# garage.net
KiCad netlist of a schematic drawn in EAGLE
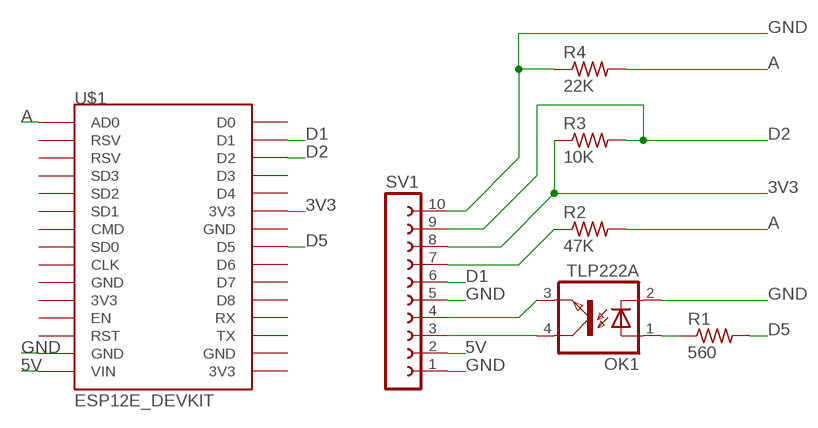
[diagram p0: schematic, sheet 1]

(export (version "E")
  (design (tool "Eeschema 10.0.6"))
  (components
    (comp (ref "OK1")
      (value "TLP222A")
      (footprint "eagle-import:DIL04")
      (libsource (lib "eagle-import") (part "TIL191"))
    )
    (comp (ref "R1")
      (value "560")
      (footprint "eagle-import:0207_7")
      (libsource (lib "eagle-import") (part "R-US_0207/7"))
    )
    (comp (ref "R2")
      (value "47K")
      (footprint "eagle-import:0207_7")
      (libsource (lib "eagle-import") (part "R-US_0207/7"))
    )
    (comp (ref "R3")
      (value "10K")
      (footprint "eagle-import:0207_7")
      (libsource (lib "eagle-import") (part "R-US_0207/7"))
    )
    (comp (ref "R4")
      (value "22K")
      (footprint "eagle-import:0207_7")
      (libsource (lib "eagle-import") (part "R-US_0207/7"))
    )
    (comp (ref "SV1")
      (value "FE10W")
      (footprint "eagle-import:FE10W")
      (libsource (lib "eagle-import") (part "FE10W"))
    )
    (comp (ref "U$1")
      (value "ESP12E_DEVKIT")
      (footprint "eagle-import:ESP12E_DEVKIT")
      (libsource (lib "eagle-import") (part "ESP12E_DEVKIT"))
    )
  )
  (nets
    (net (code "1") (name "/3V3") (class "Default")
      (node (ref "R3") (pin "1") (pinfunction "1_1") (pintype "passive"))
      (node (ref "SV1") (pin "8") (pinfunction "8_8") (pintype "passive"))
      (node (ref "U$1") (pin "3V3@1") (pinfunction "3V3_3V3@1") (pintype "bidirectional"))
    )
    (net (code "2") (name "/5V") (class "Default")
      (node (ref "SV1") (pin "2") (pinfunction "2_2") (pintype "passive"))
      (node (ref "U$1") (pin "VIN") (pinfunction "VIN_VIN") (pintype "bidirectional"))
    )
    (net (code "3") (name "/A") (class "Default")
      (node (ref "R2") (pin "2") (pinfunction "2_2") (pintype "passive"))
      (node (ref "R4") (pin "2") (pinfunction "2_2") (pintype "passive"))
      (node (ref "U$1") (pin "AD0") (pinfunction "AD0_AD0") (pintype "bidirectional"))
    )
    (net (code "4") (name "/D1") (class "Default")
      (node (ref "SV1") (pin "6") (pinfunction "6_6") (pintype "passive"))
      (node (ref "U$1") (pin "D1") (pinfunction "D1_D1") (pintype "bidirectional"))
    )
    (net (code "5") (name "/D2") (class "Default")
      (node (ref "R3") (pin "2") (pinfunction "2_2") (pintype "passive"))
      (node (ref "SV1") (pin "9") (pinfunction "9_9") (pintype "passive"))
      (node (ref "U$1") (pin "D2") (pinfunction "D2_D2") (pintype "bidirectional"))
    )
    (net (code "6") (name "/D5") (class "Default")
      (node (ref "R1") (pin "2") (pinfunction "2_2") (pintype "passive"))
      (node (ref "U$1") (pin "D5") (pinfunction "D5_D5") (pintype "bidirectional"))
    )
    (net (code "7") (name "/GND") (class "Default")
      (node (ref "OK1") (pin "2") (pinfunction "C_2") (pintype "passive"))
      (node (ref "R4") (pin "1") (pinfunction "1_1") (pintype "passive"))
      (node (ref "SV1") (pin "1") (pinfunction "1_1") (pintype "passive"))
      (node (ref "SV1") (pin "10") (pinfunction "10_10") (pintype "passive"))
      (node (ref "SV1") (pin "5") (pinfunction "5_5") (pintype "passive"))
      (node (ref "U$1") (pin "GND@1") (pinfunction "GND_GND@1") (pintype "bidirectional"))
    )
    (net (code "8") (name "Net-(OK1-A)") (class "Default")
      (node (ref "OK1") (pin "1") (pinfunction "A_1") (pintype "passive"))
      (node (ref "R1") (pin "1") (pinfunction "1_1") (pintype "passive"))
    )
    (net (code "9") (name "Net-(OK1-COL)") (class "Default")
      (node (ref "OK1") (pin "4") (pinfunction "COL_4") (pintype "passive"))
      (node (ref "SV1") (pin "3") (pinfunction "3_3") (pintype "passive"))
    )
    (net (code "10") (name "Net-(OK1-EMIT)") (class "Default")
      (node (ref "OK1") (pin "3") (pinfunction "EMIT_3") (pintype "passive"))
      (node (ref "SV1") (pin "4") (pinfunction "4_4") (pintype "passive"))
    )
    (net (code "11") (name "Net-(R2-Pad1)") (class "Default")
      (node (ref "R2") (pin "1") (pinfunction "1_1") (pintype "passive"))
      (node (ref "SV1") (pin "7") (pinfunction "7_7") (pintype "passive"))
    )
    (net (code "12") (name "unconnected-(U$1-3V3-Pad3V3@0)") (class "Default")
      (node (ref "U$1") (pin "3V3@0") (pinfunction "3V3_3V3@0") (pintype "bidirectional"))
    )
    (net (code "13") (name "unconnected-(U$1-3V3-Pad3V3@2)") (class "Default")
      (node (ref "U$1") (pin "3V3@2") (pinfunction "3V3_3V3@2") (pintype "bidirectional"))
    )
    (net (code "14") (name "unconnected-(U$1-GND-PadGND@0)") (class "Default")
      (node (ref "U$1") (pin "GND@0") (pinfunction "GND_GND@0") (pintype "bidirectional"))
    )
    (net (code "15") (name "unconnected-(U$1-GND-PadGND@2)") (class "Default")
      (node (ref "U$1") (pin "GND@2") (pinfunction "GND_GND@2") (pintype "bidirectional"))
    )
    (net (code "16") (name "unconnected-(U$1-GND-PadGND@3)") (class "Default")
      (node (ref "U$1") (pin "GND@3") (pinfunction "GND_GND@3") (pintype "bidirectional"))
    )
    (net (code "17") (name "unconnected-(U$1-PadCLK)") (class "Default")
      (node (ref "U$1") (pin "CLK") (pinfunction "CLK_CLK") (pintype "bidirectional"))
    )
    (net (code "18") (name "unconnected-(U$1-PadCMD)") (class "Default")
      (node (ref "U$1") (pin "CMD") (pinfunction "CMD_CMD") (pintype "bidirectional"))
    )
    (net (code "19") (name "unconnected-(U$1-PadD0)") (class "Default")
      (node (ref "U$1") (pin "D0") (pinfunction "D0_D0") (pintype "bidirectional"))
    )
    (net (code "20") (name "unconnected-(U$1-PadD3)") (class "Default")
      (node (ref "U$1") (pin "D3") (pinfunction "D3_D3") (pintype "bidirectional"))
    )
    (net (code "21") (name "unconnected-(U$1-PadD4)") (class "Default")
      (node (ref "U$1") (pin "D4") (pinfunction "D4_D4") (pintype "bidirectional"))
    )
    (net (code "22") (name "unconnected-(U$1-PadD6)") (class "Default")
      (node (ref "U$1") (pin "D6") (pinfunction "D6_D6") (pintype "bidirectional"))
    )
    (net (code "23") (name "unconnected-(U$1-PadD7)") (class "Default")
      (node (ref "U$1") (pin "D7") (pinfunction "D7_D7") (pintype "bidirectional"))
    )
    (net (code "24") (name "unconnected-(U$1-PadD8)") (class "Default")
      (node (ref "U$1") (pin "D8") (pinfunction "D8_D8") (pintype "bidirectional"))
    )
    (net (code "25") (name "unconnected-(U$1-PadEN)") (class "Default")
      (node (ref "U$1") (pin "EN") (pinfunction "EN_EN") (pintype "bidirectional"))
    )
    (net (code "26") (name "unconnected-(U$1-PadRST)") (class "Default")
      (node (ref "U$1") (pin "RST") (pinfunction "RST_RST") (pintype "bidirectional"))
    )
    (net (code "27") (name "unconnected-(U$1-PadRX)") (class "Default")
      (node (ref "U$1") (pin "RX") (pinfunction "RX_RX") (pintype "bidirectional"))
    )
    (net (code "28") (name "unconnected-(U$1-PadSD0)") (class "Default")
      (node (ref "U$1") (pin "SD0") (pinfunction "SD0_SD0") (pintype "bidirectional"))
    )
    (net (code "29") (name "unconnected-(U$1-PadSD1)") (class "Default")
      (node (ref "U$1") (pin "SD1") (pinfunction "SD1_SD1") (pintype "bidirectional"))
    )
    (net (code "30") (name "unconnected-(U$1-PadSD2)") (class "Default")
      (node (ref "U$1") (pin "SD2") (pinfunction "SD2_SD2") (pintype "bidirectional"))
    )
    (net (code "31") (name "unconnected-(U$1-PadSD3)") (class "Default")
      (node (ref "U$1") (pin "SD3") (pinfunction "SD3_SD3") (pintype "bidirectional"))
    )
    (net (code "32") (name "unconnected-(U$1-PadTX)") (class "Default")
      (node (ref "U$1") (pin "TX") (pinfunction "TX_TX") (pintype "bidirectional"))
    )
    (net (code "33") (name "unconnected-(U$1-RSV-PadRSV@0)") (class "Default")
      (node (ref "U$1") (pin "RSV@0") (pinfunction "RSV_RSV@0") (pintype "bidirectional"))
    )
    (net (code "34") (name "unconnected-(U$1-RSV-PadRSV@1)") (class "Default")
      (node (ref "U$1") (pin "RSV@1") (pinfunction "RSV_RSV@1") (pintype "bidirectional"))
    )
  )
)
